# Audio.net
KiCad netlist of a schematic drawn in Altium Designer
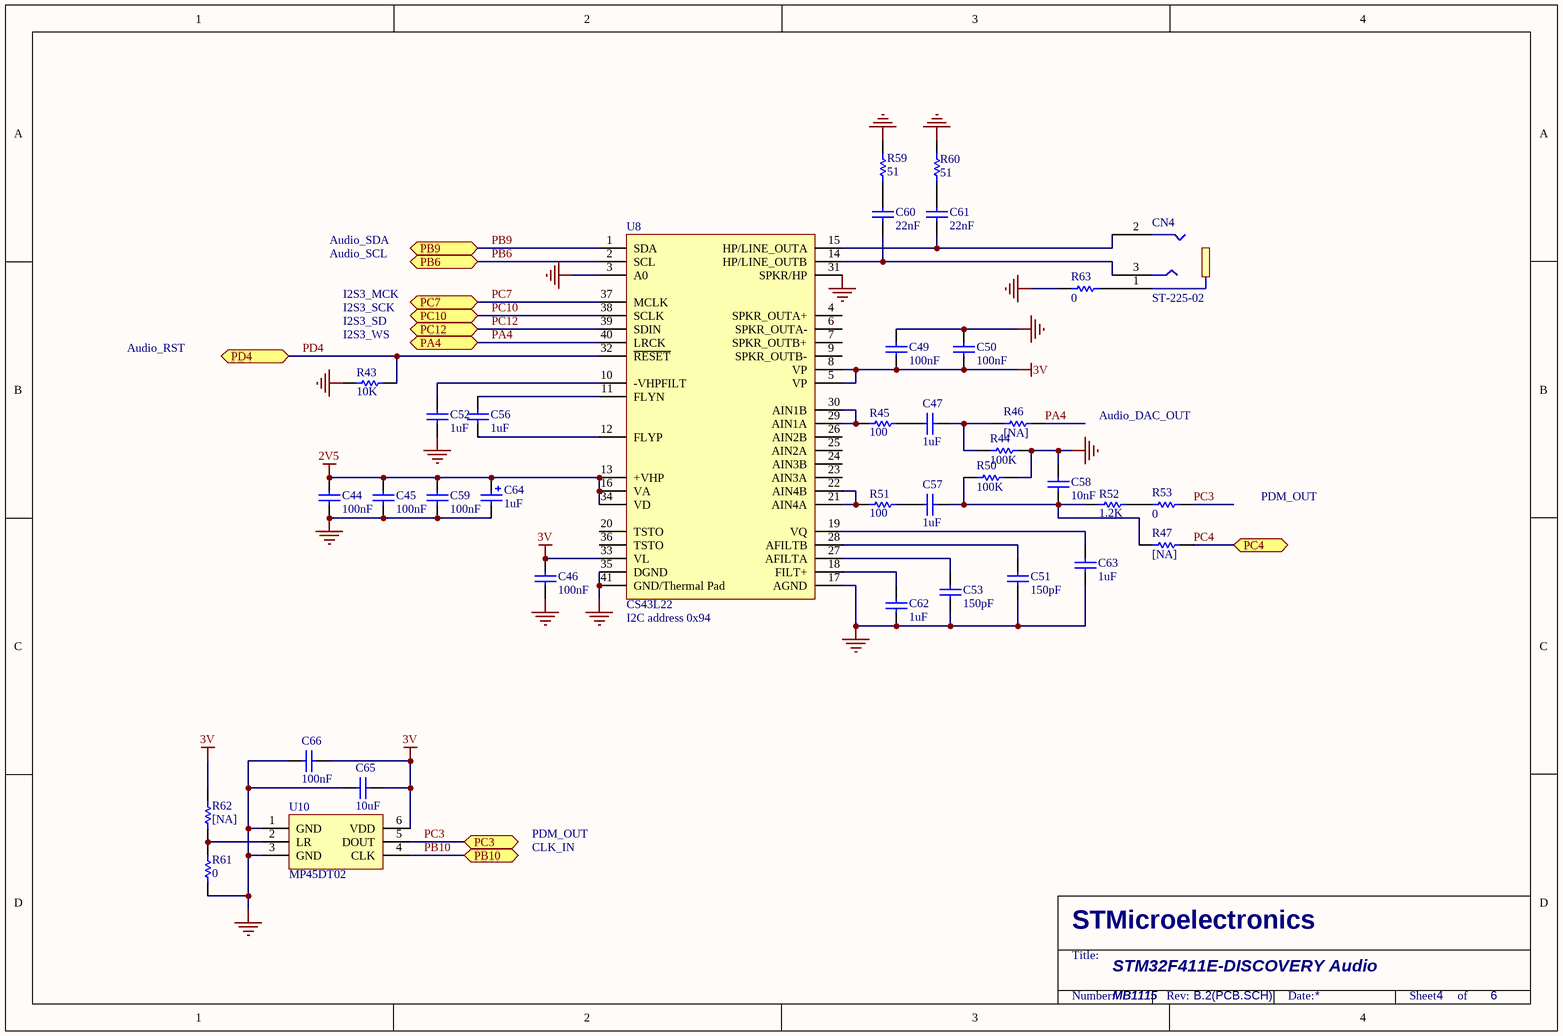
[diagram p0: Audio.SchDoc]

(export (version "E")
  (design (tool "Eeschema 10.0.6"))
  (components
    (comp (ref "C44")
      (value "100nF")
      (footprint "0402C")
      (description "Capacitor,100nF,16V,X7R,10%,0402,YAGEO")
      (libsource (lib "MCD_TOOLS") (part "Cap_100nF_X7R_10%_0402"))
    )
    (comp (ref "C45")
      (value "100nF")
      (footprint "0402C")
      (description "Capacitor,100nF,16V,X7R,10%,0402,YAGEO")
      (libsource (lib "MCD_TOOLS") (part "Cap_100nF_X7R_10%_0402"))
    )
    (comp (ref "C46")
      (value "100nF")
      (footprint "0402C")
      (description "Capacitor,100nF,16V,X7R,10%,0402,YAGEO")
      (libsource (lib "MCD_TOOLS") (part "Cap_100nF_X7R_10%_0402"))
    )
    (comp (ref "C47")
      (value "1uF")
      (footprint "0603C")
      (description "Capacitor,1uF,16V,X5R,10%,0603,YAGEO")
      (libsource (lib "MCD_TOOLS") (part "Cap_1uF_X5R_10%_0603"))
    )
    (comp (ref "C49")
      (value "100nF")
      (footprint "0402C")
      (description "Capacitor,100nF,16V,X7R,10%,0402,YAGEO")
      (libsource (lib "MCD_TOOLS") (part "Cap_100nF_X7R_10%_0402"))
    )
    (comp (ref "C50")
      (value "100nF")
      (footprint "0402C")
      (description "Capacitor,100nF,16V,X7R,10%,0402,YAGEO")
      (libsource (lib "MCD_TOOLS") (part "Cap_100nF_X7R_10%_0402"))
    )
    (comp (ref "C51")
      (value "150pF")
      (footprint "0603C")
      (description "Capacitor,150pF,50V,NPO,5%,0603,YAGEO")
      (libsource (lib "MCD_TOOLS") (part "Cap_150pF_NPO_5%_0603"))
    )
    (comp (ref "C52")
      (value "1uF")
      (footprint "0603C")
      (description "Capacitor,1uF,16V,X5R,10%,0603,YAGEO")
      (libsource (lib "MCD_TOOLS") (part "Cap_1uF_X5R_10%_0603"))
    )
    (comp (ref "C53")
      (value "150pF")
      (footprint "0603C")
      (description "Capacitor,150pF,50V,NPO,5%,0603,YAGEO")
      (libsource (lib "MCD_TOOLS") (part "Cap_150pF_NPO_5%_0603"))
    )
    (comp (ref "C56")
      (value "1uF")
      (footprint "0603C")
      (description "Capacitor,1uF,16V,X5R,10%,0603,YAGEO")
      (libsource (lib "MCD_TOOLS") (part "Cap_1uF_X5R_10%_0603"))
    )
    (comp (ref "C57")
      (value "1uF")
      (footprint "0603C")
      (description "Capacitor,1uF,16V,X5R,10%,0603,YAGEO")
      (libsource (lib "MCD_TOOLS") (part "Cap_1uF_X5R_10%_0603"))
    )
    (comp (ref "C58")
      (value "10nF")
      (footprint "0603C")
      (description "Capacitor,10nF,50V,X7R,10%,0603,YAGEO")
      (libsource (lib "MCD_TOOLS") (part "Cap_10nF_X7R_10%_0603"))
    )
    (comp (ref "C59")
      (value "100nF")
      (footprint "0402C")
      (description "Capacitor,100nF,16V,X7R,10%,0402,YAGEO")
      (libsource (lib "MCD_TOOLS") (part "Cap_100nF_X7R_10%_0402"))
    )
    (comp (ref "C60")
      (value "22nF")
      (footprint "0603C")
      (description "Capacitor,22nF,50V,X7R,10%,0603,YAGEO")
      (libsource (lib "MCD_TOOLS") (part "Cap_22nF_X7R_10%_0603"))
    )
    (comp (ref "C61")
      (value "22nF")
      (footprint "0603C")
      (description "Capacitor,22nF,50V,X7R,10%,0603,YAGEO")
      (libsource (lib "MCD_TOOLS") (part "Cap_22nF_X7R_10%_0603"))
    )
    (comp (ref "C62")
      (value "1uF")
      (footprint "0603C")
      (description "Capacitor,1uF,16V,X5R,10%,0603,YAGEO")
      (libsource (lib "MCD_TOOLS") (part "Cap_1uF_X5R_10%_0603"))
    )
    (comp (ref "C63")
      (value "1uF")
      (footprint "0603C")
      (description "Capacitor,1uF,16V,X5R,10%,0603,YAGEO")
      (libsource (lib "MCD_TOOLS") (part "Cap_1uF_X5R_10%_0603"))
    )
    (comp (ref "C64")
      (value "1uF")
      (footprint "TAN-A")
      (description "Polarized Capacitor,1uF,16V,10%,typeA,AVX")
      (libsource (lib "MCD_TOOLS") (part "Cap_1uF_POL_10%_TANA"))
    )
    (comp (ref "C65")
      (value "10uF")
      (footprint "0603C")
      (description "Capacitor,10uF,6.3V,X5R,20%,0603,YAGEO")
      (libsource (lib "MCD_TOOLS") (part "Cap_10uF_X5R_10%_0603"))
    )
    (comp (ref "C66")
      (value "100nF")
      (footprint "0402C")
      (description "Capacitor,100nF,16V,X7R,10%,0402,YAGEO")
      (libsource (lib "MCD_TOOLS") (part "Cap_100nF_X7R_10%_0402"))
    )
    (comp (ref "CN4")
      (value "ST-225-02")
      (footprint "Jack-ST-225")
      (description "Connector Jack 35mm")
      (libsource (lib "MB997") (part "ST-225-02"))
    )
    (comp (ref "R43")
      (value "10K")
      (footprint "0402R")
      (description "Resistor")
      (fields (field (name "PUBLISHER") "Altium Limited"))
      (libsource (lib "Miscellaneous Devices") (part "res1"))
    )
    (comp (ref "R44")
      (value "100K")
      (footprint "0402R")
      (description "Resistor")
      (fields (field (name "PUBLISHER") "Altium Limited"))
      (libsource (lib "Miscellaneous Devices") (part "res1"))
    )
    (comp (ref "R45")
      (value "100")
      (footprint "0402R")
      (description "Resistor")
      (fields (field (name "PUBLISHER") "Altium Limited"))
      (libsource (lib "Miscellaneous Devices") (part "res1"))
    )
    (comp (ref "R46")
      (value "[NA]")
      (footprint "STM-SMEE:0402R")
      (description "Resistor,[NA],0402")
      (libsource (lib "MCD_TOOLS") (part "Res_NA_0402"))
    )
    (comp (ref "R47")
      (value "[NA]")
      (footprint "STM-SMEE:0402R")
      (description "Resistor,[NA],0402")
      (libsource (lib "MCD_TOOLS") (part "Res_NA_0402"))
    )
    (comp (ref "R50")
      (value "100K")
      (footprint "0402R")
      (description "Resistor")
      (fields (field (name "PUBLISHER") "Altium Limited"))
      (libsource (lib "Miscellaneous Devices") (part "res1"))
    )
    (comp (ref "R51")
      (value "100")
      (footprint "0402R")
      (description "Resistor")
      (fields (field (name "PUBLISHER") "Altium Limited"))
      (libsource (lib "Miscellaneous Devices") (part "res1"))
    )
    (comp (ref "R52")
      (value "1.2K")
      (footprint "0402R")
      (description "Resistor")
      (fields (field (name "PUBLISHER") "Altium Limited"))
      (libsource (lib "Miscellaneous Devices") (part "res1"))
    )
    (comp (ref "R53")
      (value "0")
      (footprint "STM-SMEE:0402R")
      (description "Resistor,0,0402")
      (libsource (lib "MCD_TOOLS") (part "Res_0_0402"))
    )
    (comp (ref "R59")
      (value "51")
      (footprint "0402R")
      (description "Resistor")
      (fields (field (name "PUBLISHER") "Altium Limited"))
      (libsource (lib "Miscellaneous Devices") (part "res1"))
    )
    (comp (ref "R60")
      (value "51")
      (footprint "0402R")
      (description "Resistor")
      (fields (field (name "PUBLISHER") "Altium Limited"))
      (libsource (lib "Miscellaneous Devices") (part "res1"))
    )
    (comp (ref "R61")
      (value "0")
      (footprint "STM-SMEE:0402R")
      (description "Resistor,0,0402")
      (libsource (lib "MCD_TOOLS") (part "Res_0_0402"))
    )
    (comp (ref "R62")
      (value "[NA]")
      (footprint "STM-SMEE:0402R")
      (description "Resistor,[NA],0402")
      (libsource (lib "MCD_TOOLS") (part "Res_NA_0402"))
    )
    (comp (ref "R63")
      (value "0")
      (footprint "STM-SMEE:0402R")
      (description "Resistor,0,0402")
      (libsource (lib "MCD_TOOLS") (part "Res_0_0402"))
    )
    (comp (ref "U8")
      (value "CS43L22")
      (footprint "QFN40")
      (description "Low Power, Stereo DAC w/Headphone & Speaker Amps")
      (libsource (lib "MCD_TOOLS") (part "CS43L22"))
    )
    (comp (ref "U10")
      (value "MP45DT02")
      (footprint "HLGA-4.72-3.76-6LD")
      (description "MEMS audio sensor, omnidirectional digital microphone")
      (libsource (lib "MCD_TOOLS") (part "MP45DT02"))
    )
  )
  (nets
    (net (code "1") (name "/PA4") (class "Default")
      (node (ref "R46") (pin "2") (pinfunction "2_2") (pintype "passive"))
      (node (ref "U8") (pin "40") (pinfunction "LRCK_40") (pintype "passive"))
    )
    (net (code "2") (name "/PB6") (class "Default")
      (node (ref "U8") (pin "2") (pinfunction "SCL_2") (pintype "passive"))
    )
    (net (code "3") (name "/PB9") (class "Default")
      (node (ref "U8") (pin "1") (pinfunction "SDA_1") (pintype "passive"))
    )
    (net (code "4") (name "/PB10") (class "Default")
      (node (ref "U10") (pin "4") (pinfunction "CLK_4") (pintype "passive"))
    )
    (net (code "5") (name "/PC3") (class "Default")
      (node (ref "R53") (pin "2") (pinfunction "2_2") (pintype "passive"))
      (node (ref "U10") (pin "5") (pinfunction "DOUT_5") (pintype "passive"))
    )
    (net (code "6") (name "/PC4") (class "Default")
      (node (ref "R47") (pin "2") (pinfunction "2_2") (pintype "passive"))
    )
    (net (code "7") (name "/PC7") (class "Default")
      (node (ref "U8") (pin "37") (pinfunction "MCLK_37") (pintype "passive"))
    )
    (net (code "8") (name "/PC10") (class "Default")
      (node (ref "U8") (pin "38") (pinfunction "SCLK_38") (pintype "passive"))
    )
    (net (code "9") (name "/PC12") (class "Default")
      (node (ref "U8") (pin "39") (pinfunction "SDIN_39") (pintype "passive"))
    )
    (net (code "10") (name "/PD4") (class "Default")
      (node (ref "R43") (pin "1") (pinfunction "1_1") (pintype "passive"))
      (node (ref "U8") (pin "32") (pinfunction "~{RESET}_32") (pintype "passive"))
    )
    (net (code "11") (name "2V5") (class "Default")
      (node (ref "C44") (pin "2") (pinfunction "2_2") (pintype "passive"))
      (node (ref "C45") (pin "2") (pinfunction "2_2") (pintype "passive"))
      (node (ref "C59") (pin "2") (pinfunction "2_2") (pintype "passive"))
      (node (ref "C64") (pin "1") (pinfunction "1_1") (pintype "passive"))
      (node (ref "U8") (pin "13") (pinfunction "+VHP_13") (pintype "passive"))
      (node (ref "U8") (pin "16") (pinfunction "VA_16") (pintype "passive"))
      (node (ref "U8") (pin "34") (pinfunction "VD_34") (pintype "passive"))
    )
    (net (code "12") (name "3V") (class "Default")
      (node (ref "C46") (pin "2") (pinfunction "2_2") (pintype "passive"))
      (node (ref "C49") (pin "1") (pinfunction "1_1") (pintype "passive"))
      (node (ref "C50") (pin "2") (pinfunction "2_2") (pintype "passive"))
      (node (ref "C65") (pin "2") (pinfunction "2_2") (pintype "passive"))
      (node (ref "C66") (pin "2") (pinfunction "2_2") (pintype "passive"))
      (node (ref "R62") (pin "2") (pinfunction "2_2") (pintype "passive"))
      (node (ref "U10") (pin "6") (pinfunction "VDD_6") (pintype "power_in"))
      (node (ref "U8") (pin "33") (pinfunction "VL_33") (pintype "passive"))
      (node (ref "U8") (pin "5") (pinfunction "VP_5") (pintype "passive"))
      (node (ref "U8") (pin "8") (pinfunction "VP_8") (pintype "passive"))
    )
    (net (code "13") (name "GND") (class "Default")
      (node (ref "C44") (pin "1") (pinfunction "1_1") (pintype "passive"))
      (node (ref "C45") (pin "1") (pinfunction "1_1") (pintype "passive"))
      (node (ref "C46") (pin "1") (pinfunction "1_1") (pintype "passive"))
      (node (ref "C49") (pin "2") (pinfunction "2_2") (pintype "passive"))
      (node (ref "C50") (pin "1") (pinfunction "1_1") (pintype "passive"))
      (node (ref "C51") (pin "1") (pinfunction "1_1") (pintype "passive"))
      (node (ref "C52") (pin "2") (pinfunction "2_2") (pintype "passive"))
      (node (ref "C53") (pin "1") (pinfunction "1_1") (pintype "passive"))
      (node (ref "C58") (pin "2") (pinfunction "2_2") (pintype "passive"))
      (node (ref "C59") (pin "1") (pinfunction "1_1") (pintype "passive"))
      (node (ref "C62") (pin "1") (pinfunction "1_1") (pintype "passive"))
      (node (ref "C63") (pin "1") (pinfunction "1_1") (pintype "passive"))
      (node (ref "C64") (pin "2") (pinfunction "2_2") (pintype "passive"))
      (node (ref "C65") (pin "1") (pinfunction "1_1") (pintype "passive"))
      (node (ref "C66") (pin "1") (pinfunction "1_1") (pintype "passive"))
      (node (ref "R43") (pin "2") (pinfunction "2_2") (pintype "passive"))
      (node (ref "R44") (pin "2") (pinfunction "2_2") (pintype "passive"))
      (node (ref "R50") (pin "2") (pinfunction "2_2") (pintype "passive"))
      (node (ref "R59") (pin "2") (pinfunction "2_2") (pintype "passive"))
      (node (ref "R60") (pin "1") (pinfunction "1_1") (pintype "passive"))
      (node (ref "R61") (pin "1") (pinfunction "1_1") (pintype "passive"))
      (node (ref "R63") (pin "1") (pinfunction "1_1") (pintype "passive"))
      (node (ref "U10") (pin "1") (pinfunction "GND_1") (pintype "passive"))
      (node (ref "U10") (pin "3") (pinfunction "GND_3") (pintype "passive"))
      (node (ref "U8") (pin "17") (pinfunction "AGND_17") (pintype "passive"))
      (node (ref "U8") (pin "3") (pinfunction "A0_3") (pintype "passive"))
      (node (ref "U8") (pin "31") (pinfunction "SPKR/HP_31") (pintype "passive"))
      (node (ref "U8") (pin "35") (pinfunction "DGND_35") (pintype "passive"))
      (node (ref "U8") (pin "41") (pinfunction "GND/Thermal_Pad_41") (pintype "passive"))
    )
    (net (code "14") (name "Net-(C47-Pad1)") (class "Default")
      (node (ref "C47") (pin "1") (pinfunction "1_1") (pintype "passive"))
      (node (ref "R45") (pin "1") (pinfunction "1_1") (pintype "passive"))
    )
    (net (code "15") (name "Net-(C47-Pad2)") (class "Default")
      (node (ref "C47") (pin "2") (pinfunction "2_2") (pintype "passive"))
      (node (ref "R44") (pin "1") (pinfunction "1_1") (pintype "passive"))
      (node (ref "R46") (pin "1") (pinfunction "1_1") (pintype "passive"))
    )
    (net (code "16") (name "Net-(C57-Pad1)") (class "Default")
      (node (ref "C57") (pin "1") (pinfunction "1_1") (pintype "passive"))
      (node (ref "R51") (pin "1") (pinfunction "1_1") (pintype "passive"))
    )
    (net (code "17") (name "Net-(C57-Pad2)") (class "Default")
      (node (ref "C57") (pin "2") (pinfunction "2_2") (pintype "passive"))
      (node (ref "C58") (pin "1") (pinfunction "1_1") (pintype "passive"))
      (node (ref "R47") (pin "1") (pinfunction "1_1") (pintype "passive"))
      (node (ref "R50") (pin "1") (pinfunction "1_1") (pintype "passive"))
      (node (ref "R52") (pin "1") (pinfunction "1_1") (pintype "passive"))
    )
    (net (code "18") (name "Net-(C60-Pad2)") (class "Default")
      (node (ref "C60") (pin "2") (pinfunction "2_2") (pintype "passive"))
      (node (ref "R59") (pin "1") (pinfunction "1_1") (pintype "passive"))
    )
    (net (code "19") (name "Net-(C61-Pad2)") (class "Default")
      (node (ref "C61") (pin "2") (pinfunction "2_2") (pintype "passive"))
      (node (ref "R60") (pin "2") (pinfunction "2_2") (pintype "passive"))
    )
    (net (code "20") (name "Net-(CN4-Pad1)") (class "Default")
      (node (ref "CN4") (pin "1") (pintype "passive"))
      (node (ref "R63") (pin "2") (pinfunction "2_2") (pintype "passive"))
    )
    (net (code "21") (name "Net-(R52-Pad2)") (class "Default")
      (node (ref "R52") (pin "2") (pinfunction "2_2") (pintype "passive"))
      (node (ref "R53") (pin "1") (pinfunction "1_1") (pintype "passive"))
    )
    (net (code "22") (name "Net-(U8--VHPFILT)") (class "Default")
      (node (ref "C52") (pin "1") (pinfunction "1_1") (pintype "passive"))
      (node (ref "U8") (pin "10") (pinfunction "-VHPFILT_10") (pintype "passive"))
    )
    (net (code "23") (name "Net-(U8-AFILTA)") (class "Default")
      (node (ref "C53") (pin "2") (pinfunction "2_2") (pintype "passive"))
      (node (ref "U8") (pin "27") (pinfunction "AFILTA_27") (pintype "passive"))
    )
    (net (code "24") (name "Net-(U8-AFILTB)") (class "Default")
      (node (ref "C51") (pin "2") (pinfunction "2_2") (pintype "passive"))
      (node (ref "U8") (pin "28") (pinfunction "AFILTB_28") (pintype "passive"))
    )
    (net (code "25") (name "Net-(U8-AIN1A)") (class "Default")
      (node (ref "R45") (pin "2") (pinfunction "2_2") (pintype "passive"))
      (node (ref "U8") (pin "29") (pinfunction "AIN1A_29") (pintype "passive"))
      (node (ref "U8") (pin "30") (pinfunction "AIN1B_30") (pintype "passive"))
    )
    (net (code "26") (name "Net-(U8-AIN4A)") (class "Default")
      (node (ref "R51") (pin "2") (pinfunction "2_2") (pintype "passive"))
      (node (ref "U8") (pin "21") (pinfunction "AIN4A_21") (pintype "passive"))
      (node (ref "U8") (pin "22") (pinfunction "AIN4B_22") (pintype "passive"))
    )
    (net (code "27") (name "Net-(U8-FILT+)") (class "Default")
      (node (ref "C62") (pin "2") (pinfunction "2_2") (pintype "passive"))
      (node (ref "U8") (pin "18") (pinfunction "FILT+_18") (pintype "passive"))
    )
    (net (code "28") (name "Net-(U8-FLYN)") (class "Default")
      (node (ref "C56") (pin "2") (pinfunction "2_2") (pintype "passive"))
      (node (ref "U8") (pin "11") (pinfunction "FLYN_11") (pintype "passive"))
    )
    (net (code "29") (name "Net-(U8-FLYP)") (class "Default")
      (node (ref "C56") (pin "1") (pinfunction "1_1") (pintype "passive"))
      (node (ref "U8") (pin "12") (pinfunction "FLYP_12") (pintype "passive"))
    )
    (net (code "30") (name "Net-(U8-HP{slash}LINE_OUTA)") (class "Default")
      (node (ref "C61") (pin "1") (pinfunction "1_1") (pintype "passive"))
      (node (ref "CN4") (pin "2") (pintype "passive"))
      (node (ref "U8") (pin "15") (pinfunction "HP/LINE_OUTA_15") (pintype "passive"))
    )
    (net (code "31") (name "Net-(U8-HP{slash}LINE_OUTB)") (class "Default")
      (node (ref "C60") (pin "1") (pinfunction "1_1") (pintype "passive"))
      (node (ref "CN4") (pin "3") (pintype "passive"))
      (node (ref "U8") (pin "14") (pinfunction "HP/LINE_OUTB_14") (pintype "passive"))
    )
    (net (code "32") (name "Net-(U8-VQ)") (class "Default")
      (node (ref "C63") (pin "2") (pinfunction "2_2") (pintype "passive"))
      (node (ref "U8") (pin "19") (pinfunction "VQ_19") (pintype "passive"))
    )
    (net (code "33") (name "Net-(U10-LR)") (class "Default")
      (node (ref "R61") (pin "2") (pinfunction "2_2") (pintype "passive"))
      (node (ref "R62") (pin "1") (pinfunction "1_1") (pintype "passive"))
      (node (ref "U10") (pin "2") (pinfunction "LR_2") (pintype "passive"))
    )
    (net (code "34") (name "unconnected-(U8-AIN2A-Pad25)") (class "Default")
      (node (ref "U8") (pin "25") (pinfunction "AIN2A_25") (pintype "passive"))
    )
    (net (code "35") (name "unconnected-(U8-AIN2B-Pad26)") (class "Default")
      (node (ref "U8") (pin "26") (pinfunction "AIN2B_26") (pintype "passive"))
    )
    (net (code "36") (name "unconnected-(U8-AIN3A-Pad23)") (class "Default")
      (node (ref "U8") (pin "23") (pinfunction "AIN3A_23") (pintype "passive"))
    )
    (net (code "37") (name "unconnected-(U8-AIN3B-Pad24)") (class "Default")
      (node (ref "U8") (pin "24") (pinfunction "AIN3B_24") (pintype "passive"))
    )
    (net (code "38") (name "unconnected-(U8-SPKR_OUTA+-Pad4)") (class "Default")
      (node (ref "U8") (pin "4") (pinfunction "SPKR_OUTA+_4") (pintype "passive"))
    )
    (net (code "39") (name "unconnected-(U8-SPKR_OUTA--Pad6)") (class "Default")
      (node (ref "U8") (pin "6") (pinfunction "SPKR_OUTA-_6") (pintype "passive"))
    )
    (net (code "40") (name "unconnected-(U8-SPKR_OUTB+-Pad7)") (class "Default")
      (node (ref "U8") (pin "7") (pinfunction "SPKR_OUTB+_7") (pintype "passive"))
    )
    (net (code "41") (name "unconnected-(U8-SPKR_OUTB--Pad9)") (class "Default")
      (node (ref "U8") (pin "9") (pinfunction "SPKR_OUTB-_9") (pintype "passive"))
    )
    (net (code "42") (name "unconnected-(U8-TSTO-Pad20)") (class "Default")
      (node (ref "U8") (pin "20") (pinfunction "TSTO_20") (pintype "passive"))
    )
    (net (code "43") (name "unconnected-(U8-TSTO-Pad36)") (class "Default")
      (node (ref "U8") (pin "36") (pinfunction "TSTO_36") (pintype "passive"))
    )
  )
)
